# power.net
KiCad netlist of a schematic drawn in Altium Designer
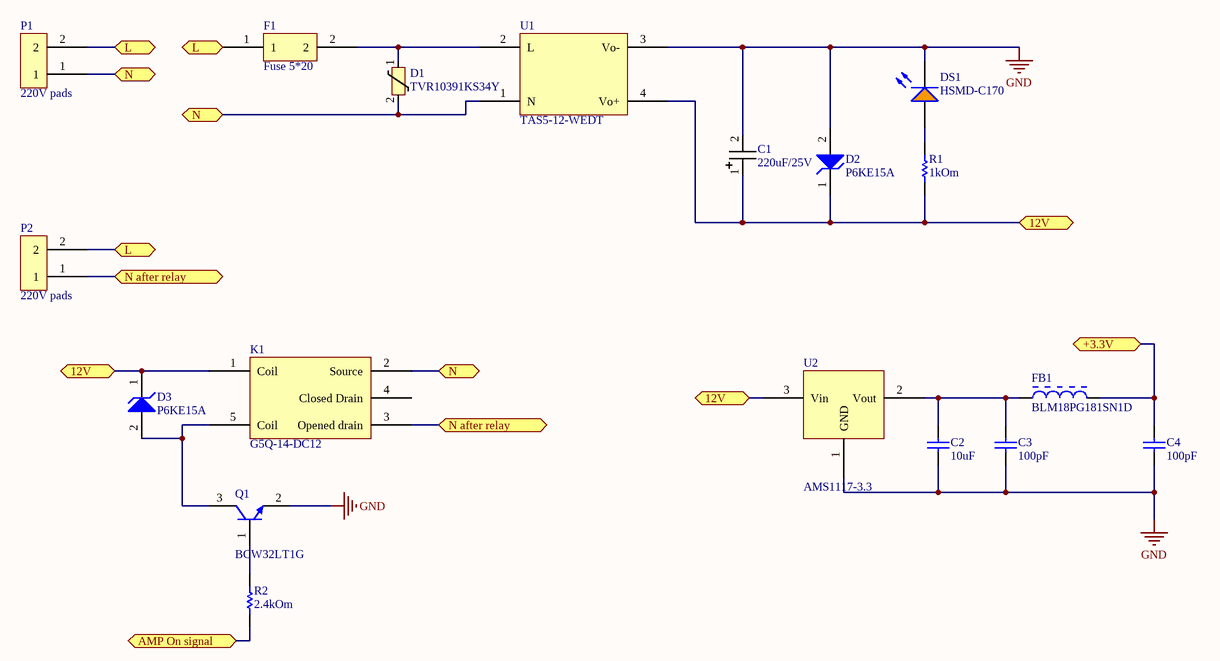
[diagram p0: power.SchDoc]

(export (version "E")
  (design (tool "Eeschema 10.0.6"))
  (components
    (comp (ref "C1")
      (value "220uF/25V")
      (footprint "Capacitor 7*8")
      (libsource (lib "Schlib1") (part "Capacitor 7*8"))
    )
    (comp (ref "C2")
      (value "10uF")
      (footprint "CAPC1608X90X35ML10T15")
      (fields (field (name "MANUFACTURER") "Murata") (field (name "PART NUMBER") "GCM1885C2A101JA16D"))
      (libsource (lib "Altium Content Vault") (part "CAP"))
    )
    (comp (ref "C3")
      (value "100pF")
      (footprint "CAPC1608X90X35ML10T15")
      (fields (field (name "MANUFACTURER") "Murata") (field (name "PART NUMBER") "GCM1885C2A101JA16D"))
      (libsource (lib "Altium Content Vault") (part "CAP"))
    )
    (comp (ref "C4")
      (value "100pF")
      (footprint "CAPC1608X90X35ML10T15")
      (fields (field (name "MANUFACTURER") "Murata") (field (name "PART NUMBER") "GCM1885C2A101JA16D"))
      (libsource (lib "Altium Content Vault") (part "CAP"))
    )
    (comp (ref "D1")
      (value "TVR10391KS34Y")
      (footprint "TVR10391KS34Y")
      (libsource (lib "Schlib1") (part "TVR10391KS34Y"))
    )
    (comp (ref "D2")
      (value "P6KE15A")
      (footprint "ONSC-SURMETIC40-2-017AA-01")
      (description "600 W Peak Power Transient Voltage Suppressor, 2-Pin Surmetic(TM) 40, Pb-Free, Bulk Box")
      (fields (field (name "MANUFACTURER") "On Semiconductor") (field (name "PARTNUMBER") "P6KE15AG"))
      (libsource (lib "Altium Content Vault") (part "ONSC-K1A2-2"))
    )
    (comp (ref "D3")
      (value "P6KE15A")
      (footprint "ONSC-SURMETIC40-2-017AA-01")
      (description "600 W Peak Power Transient Voltage Suppressor, 2-Pin Surmetic(TM) 40, Pb-Free, Bulk Box")
      (fields (field (name "MANUFACTURER") "On Semiconductor") (field (name "PARTNUMBER") "P6KE15AG"))
      (libsource (lib "Altium Content Vault") (part "ONSC-K1A2-2"))
    )
    (comp (ref "DS1")
      (value "HSMD-C170")
      (footprint "AVAG-HSMX-C170_V")
      (description "LED Uni-Color Orange, 52 mW, 20 mA, -40 to 85 degC, 2-Pin SMD, RoHS, Tape and Reel")
      (fields (field (name "MANUFACTURER") "Avago"))
      (libsource (lib "Altium Content Vault") (part "LED-ORANGE-AK-2"))
    )
    (comp (ref "F1")
      (value "Fuse 5*20")
      (footprint "Fuse 5*20")
      (libsource (lib "Schlib1") (part "Fuse 5*20"))
    )
    (comp (ref "FB1")
      (value "BLM18PG181SN1D")
      (footprint "MURA-BLM18PG_KG-CHIP-2_V2")
      (fields (field (name "MANUFACTURER") "Murata"))
      (libsource (lib "Altium Content Vault") (part "MURA-FB-2"))
    )
    (comp (ref "K1")
      (value "G5Q-14-DC12")
      (footprint "G5Q-14-DC12")
      (libsource (lib "Schlib1") (part "G5Q-14-DC12"))
    )
    (comp (ref "P1")
      (value "220V pads")
      (footprint "220V pads")
      (libsource (lib "Schlib1") (part "220V pads"))
    )
    (comp (ref "P2")
      (value "220V pads")
      (footprint "220V pads")
      (libsource (lib "Schlib1") (part "220V pads"))
    )
    (comp (ref "Q1")
      (value "BCW32LT1G")
      (footprint "ONSC-SOT-23-3-318-08_V")
      (description "General Purpose Transistor, NPN Silicon, 3-Pin SOT-23, Pb-Free, Tape and Reel")
      (fields (field (name "MANUFACTURER") "On Semiconductor"))
      (libsource (lib "Altium Content Vault") (part "ONSC-NPN-B1E2C3-3"))
    )
    (comp (ref "R1")
      (value "1kOm")
      (footprint "RESC1608X55X30ML20T10")
      (fields (field (name "PART NUMBER") "RK73H1JTTD5101F") (field (name "MANUFACTURER") "KOA Speer"))
      (libsource (lib "Altium Content Vault") (part "RES"))
    )
    (comp (ref "R2")
      (value "2.4kOm")
      (footprint "RESC1608X55X30ML20T10")
      (fields (field (name "PART NUMBER") "RK73H1JTTD5101F") (field (name "MANUFACTURER") "KOA Speer"))
      (libsource (lib "Altium Content Vault") (part "RES"))
    )
    (comp (ref "U1")
      (value "TAS5-12-WEDT")
      (footprint "TAS5-12-WEDT")
      (libsource (lib "Schlib1") (part "TAS5-12-WEDT"))
    )
    (comp (ref "U2") (value "AMS1117-3.3") (footprint "AMS1117") (libsource (lib "lib") (part "AMS1117-3.3")))
  )
  (nets
    (net (code "1") (name "/+3.3V") (class "Default")
      (node (ref "C4") (pin "2") (pinfunction "2_2") (pintype "passive"))
      (node (ref "FB1") (pin "2") (pinfunction "2_2") (pintype "passive"))
    )
    (net (code "2") (name "/12V") (class "Default")
      (node (ref "C1") (pin "1") (pintype "passive"))
      (node (ref "D2") (pin "1") (pinfunction "K_1") (pintype "passive"))
      (node (ref "D3") (pin "1") (pinfunction "K_1") (pintype "passive"))
      (node (ref "K1") (pin "1") (pinfunction "Coil_1") (pintype "passive"))
      (node (ref "R1") (pin "1") (pinfunction "1_1") (pintype "passive"))
      (node (ref "U1") (pin "4") (pinfunction "Vo+_4") (pintype "passive"))
      (node (ref "U2") (pin "3") (pinfunction "Vin_3") (pintype "passive"))
    )
    (net (code "3") (name "/AMP On signal") (class "Default")
      (node (ref "R2") (pin "1") (pinfunction "1_1") (pintype "passive"))
    )
    (net (code "4") (name "/L") (class "Default")
      (node (ref "F1") (pin "1") (pinfunction "1_1") (pintype "passive"))
      (node (ref "P1") (pin "2") (pinfunction "2_2") (pintype "passive"))
      (node (ref "P2") (pin "2") (pinfunction "2_2") (pintype "passive"))
    )
    (net (code "5") (name "/N") (class "Default")
      (node (ref "D1") (pin "2") (pintype "passive"))
      (node (ref "K1") (pin "2") (pinfunction "Source_2") (pintype "passive"))
      (node (ref "P1") (pin "1") (pinfunction "1_1") (pintype "passive"))
      (node (ref "U1") (pin "1") (pinfunction "N_1") (pintype "passive"))
    )
    (net (code "6") (name "/N after relay") (class "Default")
      (node (ref "K1") (pin "3") (pinfunction "Opened_drain_3") (pintype "passive"))
      (node (ref "P2") (pin "1") (pinfunction "1_1") (pintype "passive"))
    )
    (net (code "7") (name "GND") (class "Default")
      (node (ref "C1") (pin "2") (pintype "passive"))
      (node (ref "C2") (pin "1") (pinfunction "1_1") (pintype "passive"))
      (node (ref "C3") (pin "1") (pinfunction "1_1") (pintype "passive"))
      (node (ref "C4") (pin "1") (pinfunction "1_1") (pintype "passive"))
      (node (ref "D2") (pin "2") (pinfunction "A_2") (pintype "passive"))
      (node (ref "DS1") (pin "2") (pinfunction "K_2") (pintype "passive"))
      (node (ref "Q1") (pin "2") (pinfunction "E_2") (pintype "passive"))
      (node (ref "U1") (pin "3") (pinfunction "Vo-_3") (pintype "passive"))
      (node (ref "U2") (pin "1") (pinfunction "GND_1") (pintype "passive"))
    )
    (net (code "8") (name "Net-(D3-A)") (class "Default")
      (node (ref "D3") (pin "2") (pinfunction "A_2") (pintype "passive"))
      (node (ref "K1") (pin "5") (pinfunction "Coil_5") (pintype "passive"))
      (node (ref "Q1") (pin "3") (pinfunction "C_3") (pintype "passive"))
    )
    (net (code "9") (name "Net-(DS1-A)") (class "Default")
      (node (ref "DS1") (pin "1") (pinfunction "A_1") (pintype "passive"))
      (node (ref "R1") (pin "2") (pinfunction "2_2") (pintype "passive"))
    )
    (net (code "10") (name "Net-(Q1-B)") (class "Default")
      (node (ref "Q1") (pin "1") (pinfunction "B_1") (pintype "passive"))
      (node (ref "R2") (pin "2") (pinfunction "2_2") (pintype "passive"))
    )
    (net (code "11") (name "Net-(U1-L)") (class "Default")
      (node (ref "D1") (pin "1") (pintype "passive"))
      (node (ref "F1") (pin "2") (pinfunction "2_2") (pintype "passive"))
      (node (ref "U1") (pin "2") (pinfunction "L_2") (pintype "passive"))
    )
    (net (code "12") (name "Net-(U2-Vout)") (class "Default")
      (node (ref "C2") (pin "2") (pinfunction "2_2") (pintype "passive"))
      (node (ref "C3") (pin "2") (pinfunction "2_2") (pintype "passive"))
      (node (ref "FB1") (pin "1") (pinfunction "1_1") (pintype "passive"))
      (node (ref "U2") (pin "2") (pinfunction "Vout_2") (pintype "passive"))
    )
    (net (code "13") (name "unconnected-(K1-Closed_Drain-Pad4)") (class "Default")
      (node (ref "K1") (pin "4") (pinfunction "Closed_Drain_4") (pintype "passive"))
    )
  )
)
